# LoRa_Radio.net
KiCad netlist of a schematic drawn in Altium Designer
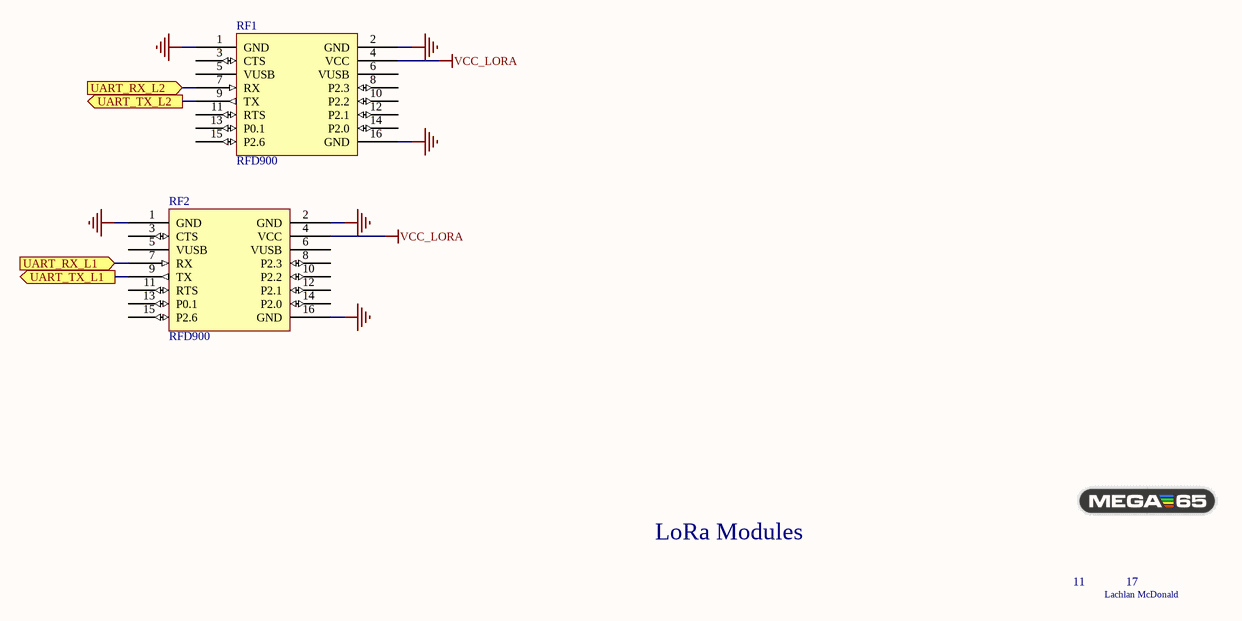
[diagram p0: LoRa Radio.SchDoc]

(export (version "E")
  (design (tool "Eeschema 10.0.6"))
  (components
    (comp (ref "RF1") (value "RFD900") (footprint "RFD900") (libsource (lib "RFD900X") (part "RFD900")))
    (comp (ref "RF2") (value "RFD900") (footprint "RFD900") (libsource (lib "RFD900X") (part "RFD900")))
  )
  (nets
    (net (code "1") (name "/UART_RX_L1") (class "Default")
      (node (ref "RF2") (pin "7") (pinfunction "RX_7") (pintype "input"))
    )
    (net (code "2") (name "/UART_RX_L2") (class "Default")
      (node (ref "RF1") (pin "7") (pinfunction "RX_7") (pintype "input"))
    )
    (net (code "3") (name "/UART_TX_L1") (class "Default")
      (node (ref "RF2") (pin "9") (pinfunction "TX_9") (pintype "output"))
    )
    (net (code "4") (name "/UART_TX_L2") (class "Default")
      (node (ref "RF1") (pin "9") (pinfunction "TX_9") (pintype "output"))
    )
    (net (code "5") (name "GND") (class "Default")
      (node (ref "RF1") (pin "1") (pinfunction "GND_1") (pintype "power_in"))
      (node (ref "RF1") (pin "16") (pinfunction "GND_16") (pintype "power_in"))
      (node (ref "RF1") (pin "2") (pinfunction "GND_2") (pintype "power_in"))
      (node (ref "RF2") (pin "1") (pinfunction "GND_1") (pintype "power_in"))
      (node (ref "RF2") (pin "16") (pinfunction "GND_16") (pintype "power_in"))
      (node (ref "RF2") (pin "2") (pinfunction "GND_2") (pintype "power_in"))
    )
    (net (code "6") (name "VCC_LORA") (class "Default")
      (node (ref "RF1") (pin "4") (pinfunction "VCC_4") (pintype "power_in"))
      (node (ref "RF2") (pin "4") (pinfunction "VCC_4") (pintype "power_in"))
    )
    (net (code "7") (name "unconnected-(RF1-CTS-Pad3)") (class "Default")
      (node (ref "RF1") (pin "3") (pinfunction "CTS_3") (pintype "bidirectional"))
    )
    (net (code "8") (name "unconnected-(RF1-P0.1-Pad13)") (class "Default")
      (node (ref "RF1") (pin "13") (pinfunction "P0.1_13") (pintype "bidirectional"))
    )
    (net (code "9") (name "unconnected-(RF1-P2.0-Pad14)") (class "Default")
      (node (ref "RF1") (pin "14") (pinfunction "P2.0_14") (pintype "bidirectional"))
    )
    (net (code "10") (name "unconnected-(RF1-P2.1-Pad12)") (class "Default")
      (node (ref "RF1") (pin "12") (pinfunction "P2.1_12") (pintype "bidirectional"))
    )
    (net (code "11") (name "unconnected-(RF1-P2.2-Pad10)") (class "Default")
      (node (ref "RF1") (pin "10") (pinfunction "P2.2_10") (pintype "bidirectional"))
    )
    (net (code "12") (name "unconnected-(RF1-P2.3-Pad8)") (class "Default")
      (node (ref "RF1") (pin "8") (pinfunction "P2.3_8") (pintype "bidirectional"))
    )
    (net (code "13") (name "unconnected-(RF1-P2.6-Pad15)") (class "Default")
      (node (ref "RF1") (pin "15") (pinfunction "P2.6_15") (pintype "bidirectional"))
    )
    (net (code "14") (name "unconnected-(RF1-RTS-Pad11)") (class "Default")
      (node (ref "RF1") (pin "11") (pinfunction "RTS_11") (pintype "bidirectional"))
    )
    (net (code "15") (name "unconnected-(RF1-VUSB-Pad5)") (class "Default")
      (node (ref "RF1") (pin "5") (pinfunction "VUSB_5") (pintype "power_in"))
    )
    (net (code "16") (name "unconnected-(RF1-VUSB-Pad6)") (class "Default")
      (node (ref "RF1") (pin "6") (pinfunction "VUSB_6") (pintype "power_in"))
    )
    (net (code "17") (name "unconnected-(RF2-CTS-Pad3)") (class "Default")
      (node (ref "RF2") (pin "3") (pinfunction "CTS_3") (pintype "bidirectional"))
    )
    (net (code "18") (name "unconnected-(RF2-P0.1-Pad13)") (class "Default")
      (node (ref "RF2") (pin "13") (pinfunction "P0.1_13") (pintype "bidirectional"))
    )
    (net (code "19") (name "unconnected-(RF2-P2.0-Pad14)") (class "Default")
      (node (ref "RF2") (pin "14") (pinfunction "P2.0_14") (pintype "bidirectional"))
    )
    (net (code "20") (name "unconnected-(RF2-P2.1-Pad12)") (class "Default")
      (node (ref "RF2") (pin "12") (pinfunction "P2.1_12") (pintype "bidirectional"))
    )
    (net (code "21") (name "unconnected-(RF2-P2.2-Pad10)") (class "Default")
      (node (ref "RF2") (pin "10") (pinfunction "P2.2_10") (pintype "bidirectional"))
    )
    (net (code "22") (name "unconnected-(RF2-P2.3-Pad8)") (class "Default")
      (node (ref "RF2") (pin "8") (pinfunction "P2.3_8") (pintype "bidirectional"))
    )
    (net (code "23") (name "unconnected-(RF2-P2.6-Pad15)") (class "Default")
      (node (ref "RF2") (pin "15") (pinfunction "P2.6_15") (pintype "bidirectional"))
    )
    (net (code "24") (name "unconnected-(RF2-RTS-Pad11)") (class "Default")
      (node (ref "RF2") (pin "11") (pinfunction "RTS_11") (pintype "bidirectional"))
    )
    (net (code "25") (name "unconnected-(RF2-VUSB-Pad5)") (class "Default")
      (node (ref "RF2") (pin "5") (pinfunction "VUSB_5") (pintype "power_in"))
    )
    (net (code "26") (name "unconnected-(RF2-VUSB-Pad6)") (class "Default")
      (node (ref "RF2") (pin "6") (pinfunction "VUSB_6") (pintype "power_in"))
    )
  )
)
